# PowCarbinBoard_General.net
KiCad netlist of a schematic drawn in Altium Designer
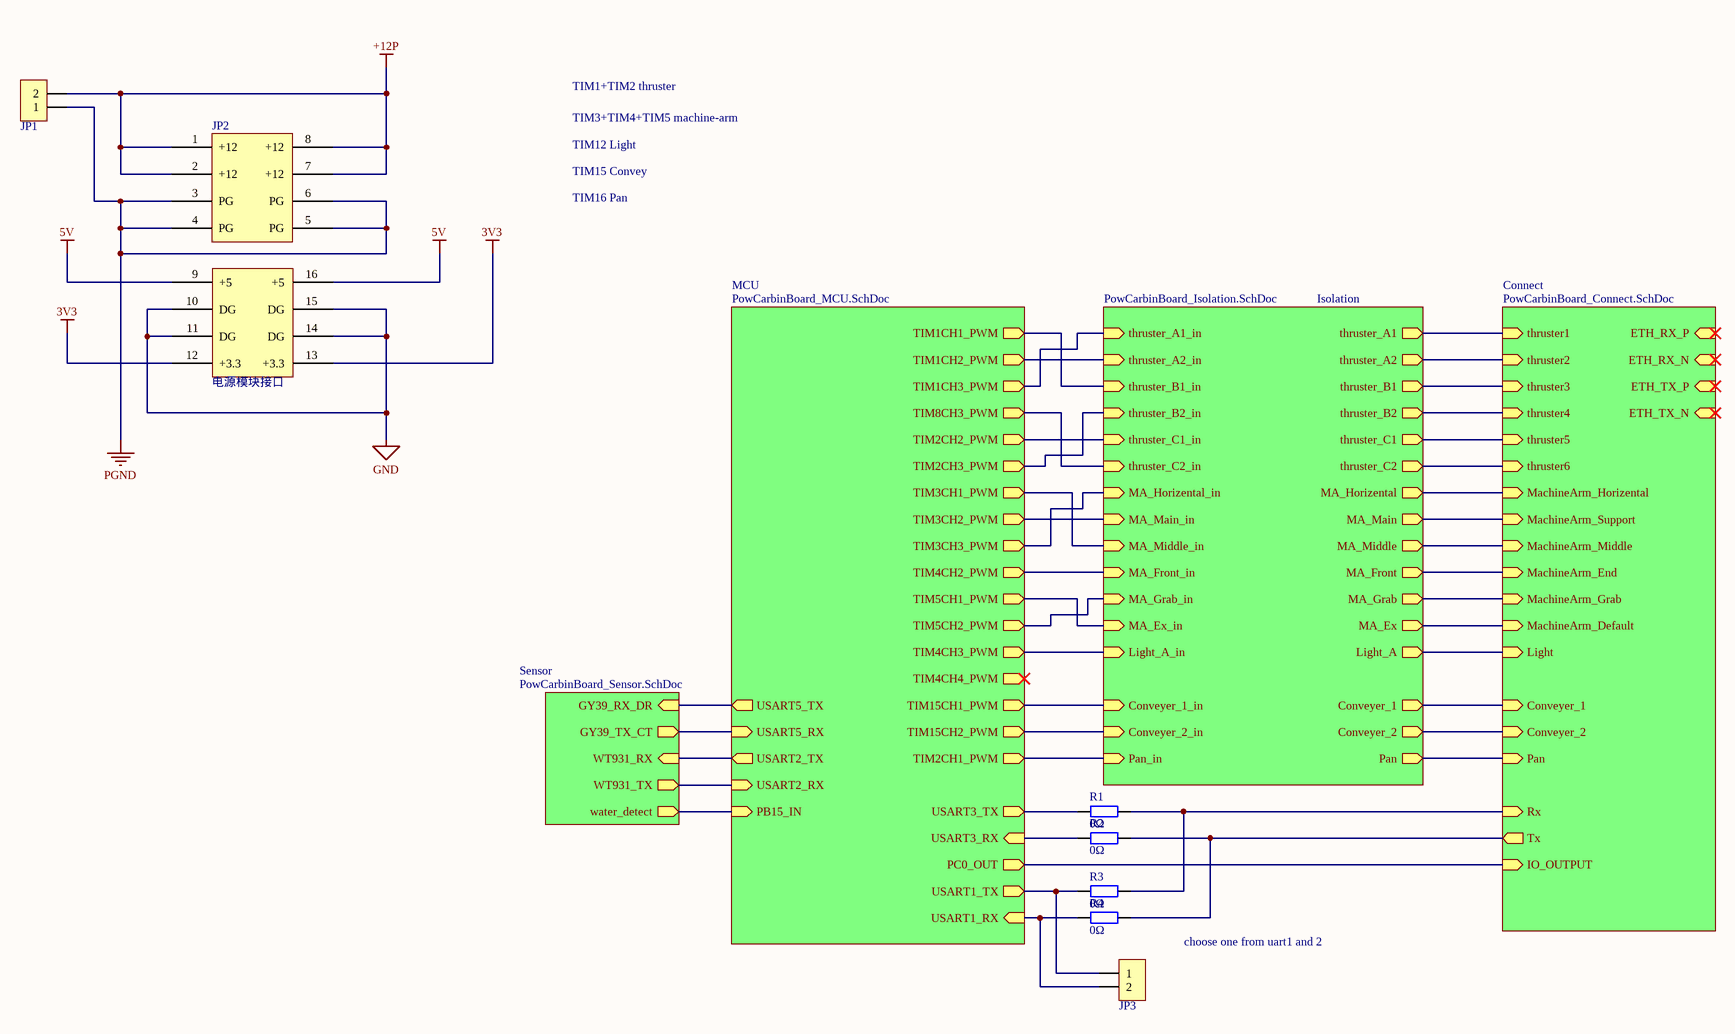
[diagram p0: PowCarbinBoard_General.SchDoc]

(export (version "E")
  (design (tool "Eeschema 10.0.6"))
  (components
    (comp (ref "JP1")
      (value "HDR-1X2")
      (footprint "KF128-5.08-2P")
      (description "2P接插件")
      (fields (field (name "版权归属") "源创客"))
      (libsource (lib "4.10 - 接插件-脚距5.08") (part "Header 2"))
    )
    (comp (ref "JP2") (value "电源模块接口") (footprint "排针-座 2*4") (libsource (lib "MySchLib") (part "电源模块接口")))
    (comp (ref "JP3")
      (value "HDR-1X2")
      (footprint "HDR2.54-LI-2P")
      (description "2P接插件")
      (fields (field (name "版权归属") "源创客"))
      (libsource (lib "4.5   - 接插件-脚距2.54") (part "Header 2"))
    )
    (comp (ref "R1")
      (value "0Ω")
      (footprint "R 0603_L")
      (description "贴片电阻")
      (fields (field (name "版权归属") "源创客"))
      (libsource (lib "3.1   - 电阻-电容-电感") (part "R"))
    )
    (comp (ref "R2")
      (value "0Ω")
      (footprint "R 0603_L")
      (description "贴片电阻")
      (fields (field (name "版权归属") "源创客"))
      (libsource (lib "3.1   - 电阻-电容-电感") (part "R"))
    )
    (comp (ref "R3")
      (value "0Ω")
      (footprint "R 0603_L")
      (description "贴片电阻")
      (fields (field (name "版权归属") "源创客"))
      (libsource (lib "3.1   - 电阻-电容-电感") (part "R"))
    )
    (comp (ref "R4")
      (value "0Ω")
      (footprint "R 0603_L")
      (description "贴片电阻")
      (fields (field (name "版权归属") "源创客"))
      (libsource (lib "3.1   - 电阻-电容-电感") (part "R"))
    )
  )
  (nets
    (net (code "1") (name "+12P") (class "Default")
      (node (ref "JP1") (pin "2") (pinfunction "2_2") (pintype "passive"))
      (node (ref "JP2") (pin "1") (pinfunction "+12_1") (pintype "passive"))
      (node (ref "JP2") (pin "2") (pinfunction "+12_2") (pintype "passive"))
      (node (ref "JP2") (pin "7") (pinfunction "+12_7") (pintype "passive"))
      (node (ref "JP2") (pin "8") (pinfunction "+12_8") (pintype "passive"))
    )
    (net (code "18") (name "/Rx") (class "Default")
      (node (ref "R1") (pin "2") (pinfunction "2_2") (pintype "passive"))
      (node (ref "R3") (pin "2") (pinfunction "2_2") (pintype "passive"))
    )
    (net (code "36") (name "/Tx") (class "Default")
      (node (ref "R2") (pin "2") (pinfunction "2_2") (pintype "passive"))
      (node (ref "R4") (pin "2") (pinfunction "2_2") (pintype "passive"))
    )
    (net (code "37") (name "/USART1_RX") (class "Default")
      (node (ref "JP3") (pin "2") (pinfunction "2_2") (pintype "passive"))
      (node (ref "R4") (pin "1") (pinfunction "1_1") (pintype "passive"))
    )
    (net (code "38") (name "/USART1_TX") (class "Default")
      (node (ref "JP3") (pin "1") (pinfunction "1_1") (pintype "passive"))
      (node (ref "R3") (pin "1") (pinfunction "1_1") (pintype "passive"))
    )
    (net (code "40") (name "/USART3_RX") (class "Default")
      (node (ref "R2") (pin "1") (pinfunction "1_1") (pintype "passive"))
    )
    (net (code "41") (name "/USART3_TX") (class "Default")
      (node (ref "R1") (pin "1") (pinfunction "1_1") (pintype "passive"))
    )
    (net (code "51") (name "3V3") (class "Default")
      (node (ref "JP2") (pin "12") (pinfunction "+3.3_12") (pintype "passive"))
      (node (ref "JP2") (pin "13") (pinfunction "+3.3_13") (pintype "passive"))
    )
    (net (code "52") (name "5V") (class "Default")
      (node (ref "JP2") (pin "16") (pinfunction "+5_16") (pintype "passive"))
      (node (ref "JP2") (pin "9") (pinfunction "+5_9") (pintype "passive"))
    )
    (net (code "53") (name "GND") (class "Default")
      (node (ref "JP2") (pin "10") (pinfunction "DG_10") (pintype "passive"))
      (node (ref "JP2") (pin "11") (pinfunction "DG_11") (pintype "passive"))
      (node (ref "JP2") (pin "14") (pinfunction "DG_14") (pintype "passive"))
      (node (ref "JP2") (pin "15") (pinfunction "DG_15") (pintype "passive"))
    )
    (net (code "54") (name "PGND") (class "Default")
      (node (ref "JP1") (pin "1") (pinfunction "1_1") (pintype "passive"))
      (node (ref "JP2") (pin "3") (pinfunction "PG_3") (pintype "passive"))
      (node (ref "JP2") (pin "4") (pinfunction "PG_4") (pintype "passive"))
      (node (ref "JP2") (pin "5") (pinfunction "PG_5") (pintype "passive"))
      (node (ref "JP2") (pin "6") (pinfunction "PG_6") (pintype "passive"))
    )
  )
)
